# test.net
KiCad netlist of a schematic drawn in EAGLE
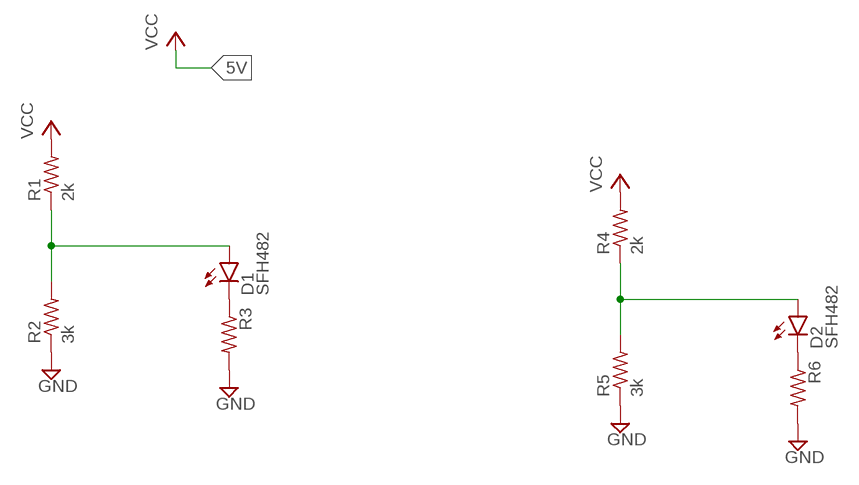
[diagram p0: schematic, sheet 1]

(export (version "E")
  (design (tool "Eeschema 10.0.6"))
  (components
    (comp (ref "D1")
      (value "SFH482")
      (footprint "eagle-import:SFH482")
      (libsource (lib "eagle-import") (part "SFH482"))
    )
    (comp (ref "D2")
      (value "SFH482")
      (footprint "eagle-import:SFH482")
      (libsource (lib "eagle-import") (part "SFH482"))
    )
    (comp (ref "R1")
      (value "2k")
      (footprint "eagle-import:0204_7")
      (libsource (lib "eagle-import") (part "R-US_0204/7"))
    )
    (comp (ref "R2")
      (value "3k")
      (footprint "eagle-import:0204_7")
      (libsource (lib "eagle-import") (part "R-US_0204/7"))
    )
    (comp (ref "R3")
      (value "R-US_0204/7")
      (footprint "eagle-import:0204_7")
      (libsource (lib "eagle-import") (part "R-US_0204/7"))
    )
    (comp (ref "R4")
      (value "2k")
      (footprint "eagle-import:0204_7")
      (libsource (lib "eagle-import") (part "R-US_0204/7"))
    )
    (comp (ref "R5")
      (value "3k")
      (footprint "eagle-import:0204_7")
      (libsource (lib "eagle-import") (part "R-US_0204/7"))
    )
    (comp (ref "R6")
      (value "R-US_0204/7")
      (footprint "eagle-import:0204_7")
      (libsource (lib "eagle-import") (part "R-US_0204/7"))
    )
  )
  (nets
    (net (code "1") (name "5V") (class "Default")
      (node (ref "R1") (pin "2") (pinfunction "2_2") (pintype "passive"))
      (node (ref "R4") (pin "2") (pinfunction "2_2") (pintype "passive"))
    )
    (net (code "2") (name "GND") (class "Default")
      (node (ref "R2") (pin "1") (pinfunction "1_1") (pintype "passive"))
      (node (ref "R3") (pin "2") (pinfunction "2_2") (pintype "passive"))
      (node (ref "R5") (pin "1") (pinfunction "1_1") (pintype "passive"))
      (node (ref "R6") (pin "2") (pinfunction "2_2") (pintype "passive"))
    )
    (net (code "3") (name "Net-(D1-C)") (class "Default")
      (node (ref "D1") (pin "K") (pinfunction "C_K") (pintype "passive"))
      (node (ref "R3") (pin "1") (pinfunction "1_1") (pintype "passive"))
    )
    (net (code "4") (name "Net-(D1-PadA)") (class "Default")
      (node (ref "D1") (pin "A") (pinfunction "A_A") (pintype "passive"))
      (node (ref "R1") (pin "1") (pinfunction "1_1") (pintype "passive"))
      (node (ref "R2") (pin "2") (pinfunction "2_2") (pintype "passive"))
    )
    (net (code "5") (name "Net-(D2-C)") (class "Default")
      (node (ref "D2") (pin "K") (pinfunction "C_K") (pintype "passive"))
      (node (ref "R6") (pin "1") (pinfunction "1_1") (pintype "passive"))
    )
    (net (code "6") (name "Net-(D2-PadA)") (class "Default")
      (node (ref "D2") (pin "A") (pinfunction "A_A") (pintype "passive"))
      (node (ref "R4") (pin "1") (pinfunction "1_1") (pintype "passive"))
      (node (ref "R5") (pin "2") (pinfunction "2_2") (pintype "passive"))
    )
  )
)
